# teplomer.net
KiCad netlist of a schematic drawn in Altium Designer
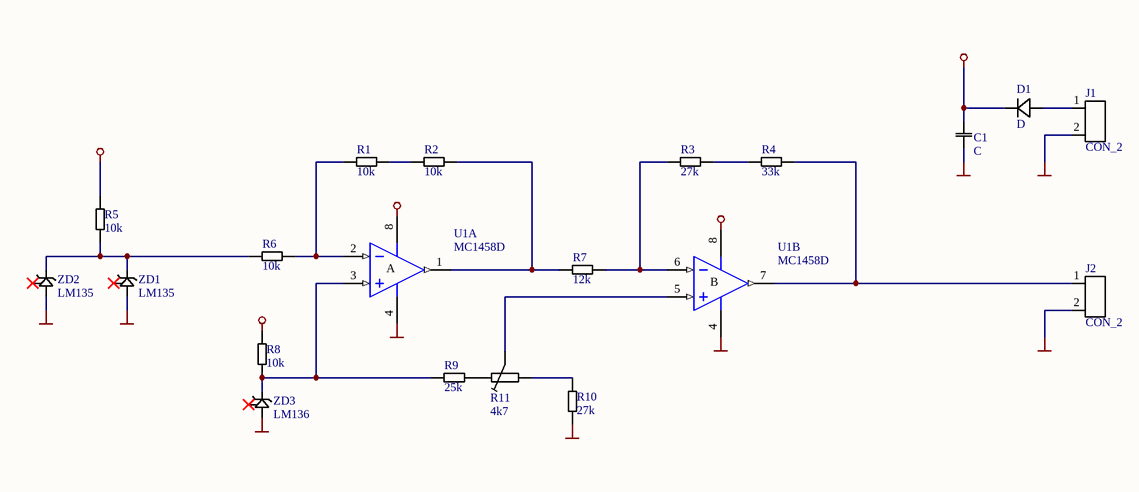
[diagram p0: teplomer.SCHDOC]

(export (version "E")
  (design (tool "Eeschema 10.0.6"))
  (components
    (comp (ref "C1") (value "C") (footprint "C0805") (libsource (lib "ABU_standard") (part "C")))
    (comp (ref "D1") (value "D") (footprint "SMA") (libsource (lib "ABU_standard") (part "D")))
    (comp (ref "J1") (value "CON_2") (footprint "ARK_2") (libsource (lib "ABU_standard") (part "CON_2")))
    (comp (ref "J2") (value "CON_2") (footprint "ARK_2") (libsource (lib "ABU_standard") (part "CON_2")))
    (comp (ref "R1") (value "10k") (footprint "R0805") (libsource (lib "ABU_standard") (part "R")))
    (comp (ref "R2") (value "10k") (footprint "R0805") (libsource (lib "ABU_standard") (part "R")))
    (comp (ref "R3") (value "27k") (footprint "R0805") (libsource (lib "ABU_standard") (part "R")))
    (comp (ref "R4") (value "33k") (footprint "R0805") (libsource (lib "ABU_standard") (part "R")))
    (comp (ref "R5") (value "10k") (footprint "R0805") (libsource (lib "") (part "R_2")))
    (comp (ref "R6") (value "10k") (footprint "R0805") (libsource (lib "ABU_standard") (part "R")))
    (comp (ref "R7") (value "12k") (footprint "R0805") (libsource (lib "ABU_standard") (part "R")))
    (comp (ref "R8") (value "10k") (footprint "R0805") (libsource (lib "") (part "R_2")))
    (comp (ref "R9") (value "25k") (footprint "R0805") (libsource (lib "") (part "R_1")))
    (comp (ref "R10") (value "27k") (footprint "R0805") (libsource (lib "") (part "R_2")))
    (comp (ref "R11") (value "4k7") (footprint "Trimr PT655") (libsource (lib "ABU_standard") (part "Trimr")))
    (comp (ref "U1")
      (value "MC1458D")
      (footprint "SO8")
      (description "Dual Operational Amplifier")
      (fields (field (name "PUBLISHER") "Altium Limited"))
      (libsource (lib "ST Operational Amplifier") (part "MC1458D"))
    )
    (comp (ref "ZD1") (value "LM135") (footprint "SO8") (libsource (lib "ABU_standard") (part "LM135")))
    (comp (ref "ZD2") (value "LM135") (footprint "TO-92") (libsource (lib "ABU_standard") (part "LM135")))
    (comp (ref "ZD3") (value "LM136") (footprint "SO8") (libsource (lib "ABU_standard") (part "LM135")))
  )
  (nets
    (net (code "1") (name "GND") (class "Default")
      (node (ref "C1") (pin "1") (pinfunction "1_1") (pintype "passive"))
      (node (ref "J1") (pin "2") (pinfunction "2_2") (pintype "passive"))
      (node (ref "J2") (pin "2") (pinfunction "2_2") (pintype "passive"))
      (node (ref "R10") (pin "2") (pinfunction "2_2") (pintype "passive"))
      (node (ref "U1") (pin "4") (pinfunction "V-_4") (pintype "power_in"))
      (node (ref "ZD1") (pin "3") (pinfunction "A_3") (pintype "passive"))
      (node (ref "ZD2") (pin "3") (pinfunction "A_3") (pintype "passive"))
      (node (ref "ZD3") (pin "3") (pinfunction "A_3") (pintype "passive"))
    )
    (net (code "2") (name "Net-(D1-A)") (class "Default")
      (node (ref "D1") (pin "1") (pinfunction "A_1") (pintype "passive"))
      (node (ref "J1") (pin "1") (pinfunction "1_1") (pintype "passive"))
    )
    (net (code "3") (name "Net-(R1-Pad1)") (class "Default")
      (node (ref "R1") (pin "1") (pinfunction "1_1") (pintype "passive"))
      (node (ref "R2") (pin "2") (pinfunction "2_2") (pintype "passive"))
    )
    (net (code "4") (name "Net-(R3-Pad1)") (class "Default")
      (node (ref "R3") (pin "1") (pinfunction "1_1") (pintype "passive"))
      (node (ref "R4") (pin "2") (pinfunction "2_2") (pintype "passive"))
    )
    (net (code "5") (name "Net-(R10-Pad1)") (class "Default")
      (node (ref "R10") (pin "1") (pinfunction "1_1") (pintype "passive"))
      (node (ref "R11") (pin "1") (pinfunction "1_1") (pintype "passive"))
    )
    (net (code "6") (name "Net-(R11-Pad2)") (class "Default")
      (node (ref "R11") (pin "2") (pinfunction "2_2") (pintype "passive"))
      (node (ref "R9") (pin "2") (pinfunction "2_2") (pintype "passive"))
    )
    (net (code "7") (name "Net-(U1A-IN+)") (class "Default")
      (node (ref "R8") (pin "2") (pinfunction "2_2") (pintype "passive"))
      (node (ref "R9") (pin "1") (pinfunction "1_1") (pintype "passive"))
      (node (ref "U1") (pin "3") (pinfunction "IN+_3") (pintype "input"))
      (node (ref "ZD3") (pin "2") (pinfunction "K_2") (pintype "passive"))
    )
    (net (code "8") (name "Net-(U1A-IN-)") (class "Default")
      (node (ref "R1") (pin "2") (pinfunction "2_2") (pintype "passive"))
      (node (ref "R6") (pin "1") (pinfunction "1_1") (pintype "passive"))
      (node (ref "U1") (pin "2") (pinfunction "IN-_2") (pintype "input"))
    )
    (net (code "9") (name "Net-(U1A-OUT)") (class "Default")
      (node (ref "R2") (pin "1") (pinfunction "1_1") (pintype "passive"))
      (node (ref "R7") (pin "2") (pinfunction "2_2") (pintype "passive"))
      (node (ref "U1") (pin "1") (pinfunction "OUT_1") (pintype "output"))
    )
    (net (code "10") (name "Net-(U1B-IN+)") (class "Default")
      (node (ref "R11") (pin "3") (pinfunction "3_3") (pintype "passive"))
      (node (ref "U1") (pin "5") (pinfunction "IN+_5") (pintype "input"))
    )
    (net (code "11") (name "Net-(U1B-IN-)") (class "Default")
      (node (ref "R3") (pin "2") (pinfunction "2_2") (pintype "passive"))
      (node (ref "R7") (pin "1") (pinfunction "1_1") (pintype "passive"))
      (node (ref "U1") (pin "6") (pinfunction "IN-_6") (pintype "input"))
    )
    (net (code "12") (name "Net-(U1B-OUT)") (class "Default")
      (node (ref "J2") (pin "1") (pinfunction "1_1") (pintype "passive"))
      (node (ref "R4") (pin "1") (pinfunction "1_1") (pintype "passive"))
      (node (ref "U1") (pin "7") (pinfunction "OUT_7") (pintype "output"))
    )
    (net (code "13") (name "Net-(ZD1-K)") (class "Default")
      (node (ref "R5") (pin "2") (pinfunction "2_2") (pintype "passive"))
      (node (ref "R6") (pin "2") (pinfunction "2_2") (pintype "passive"))
      (node (ref "ZD1") (pin "2") (pinfunction "K_2") (pintype "passive"))
      (node (ref "ZD2") (pin "2") (pinfunction "K_2") (pintype "passive"))
    )
    (net (code "14") (name "Vs") (class "Default")
      (node (ref "C1") (pin "2") (pinfunction "2_2") (pintype "passive"))
      (node (ref "D1") (pin "2") (pinfunction "K_2") (pintype "passive"))
      (node (ref "R5") (pin "1") (pinfunction "1_1") (pintype "passive"))
      (node (ref "R8") (pin "1") (pinfunction "1_1") (pintype "passive"))
      (node (ref "U1") (pin "8") (pinfunction "V+_8") (pintype "power_in"))
    )
    (net (code "15") (name "unconnected-(ZD1-ADJ-Pad1)") (class "Default")
      (node (ref "ZD1") (pin "1") (pinfunction "ADJ_1") (pintype "passive+no_connect"))
    )
    (net (code "16") (name "unconnected-(ZD2-ADJ-Pad1)") (class "Default")
      (node (ref "ZD2") (pin "1") (pinfunction "ADJ_1") (pintype "passive+no_connect"))
    )
    (net (code "17") (name "unconnected-(ZD3-ADJ-Pad1)") (class "Default")
      (node (ref "ZD3") (pin "1") (pinfunction "ADJ_1") (pintype "passive+no_connect"))
    )
  )
)
